# LIN_EXPO.net
KiCad netlist of a schematic drawn in Altium Designer
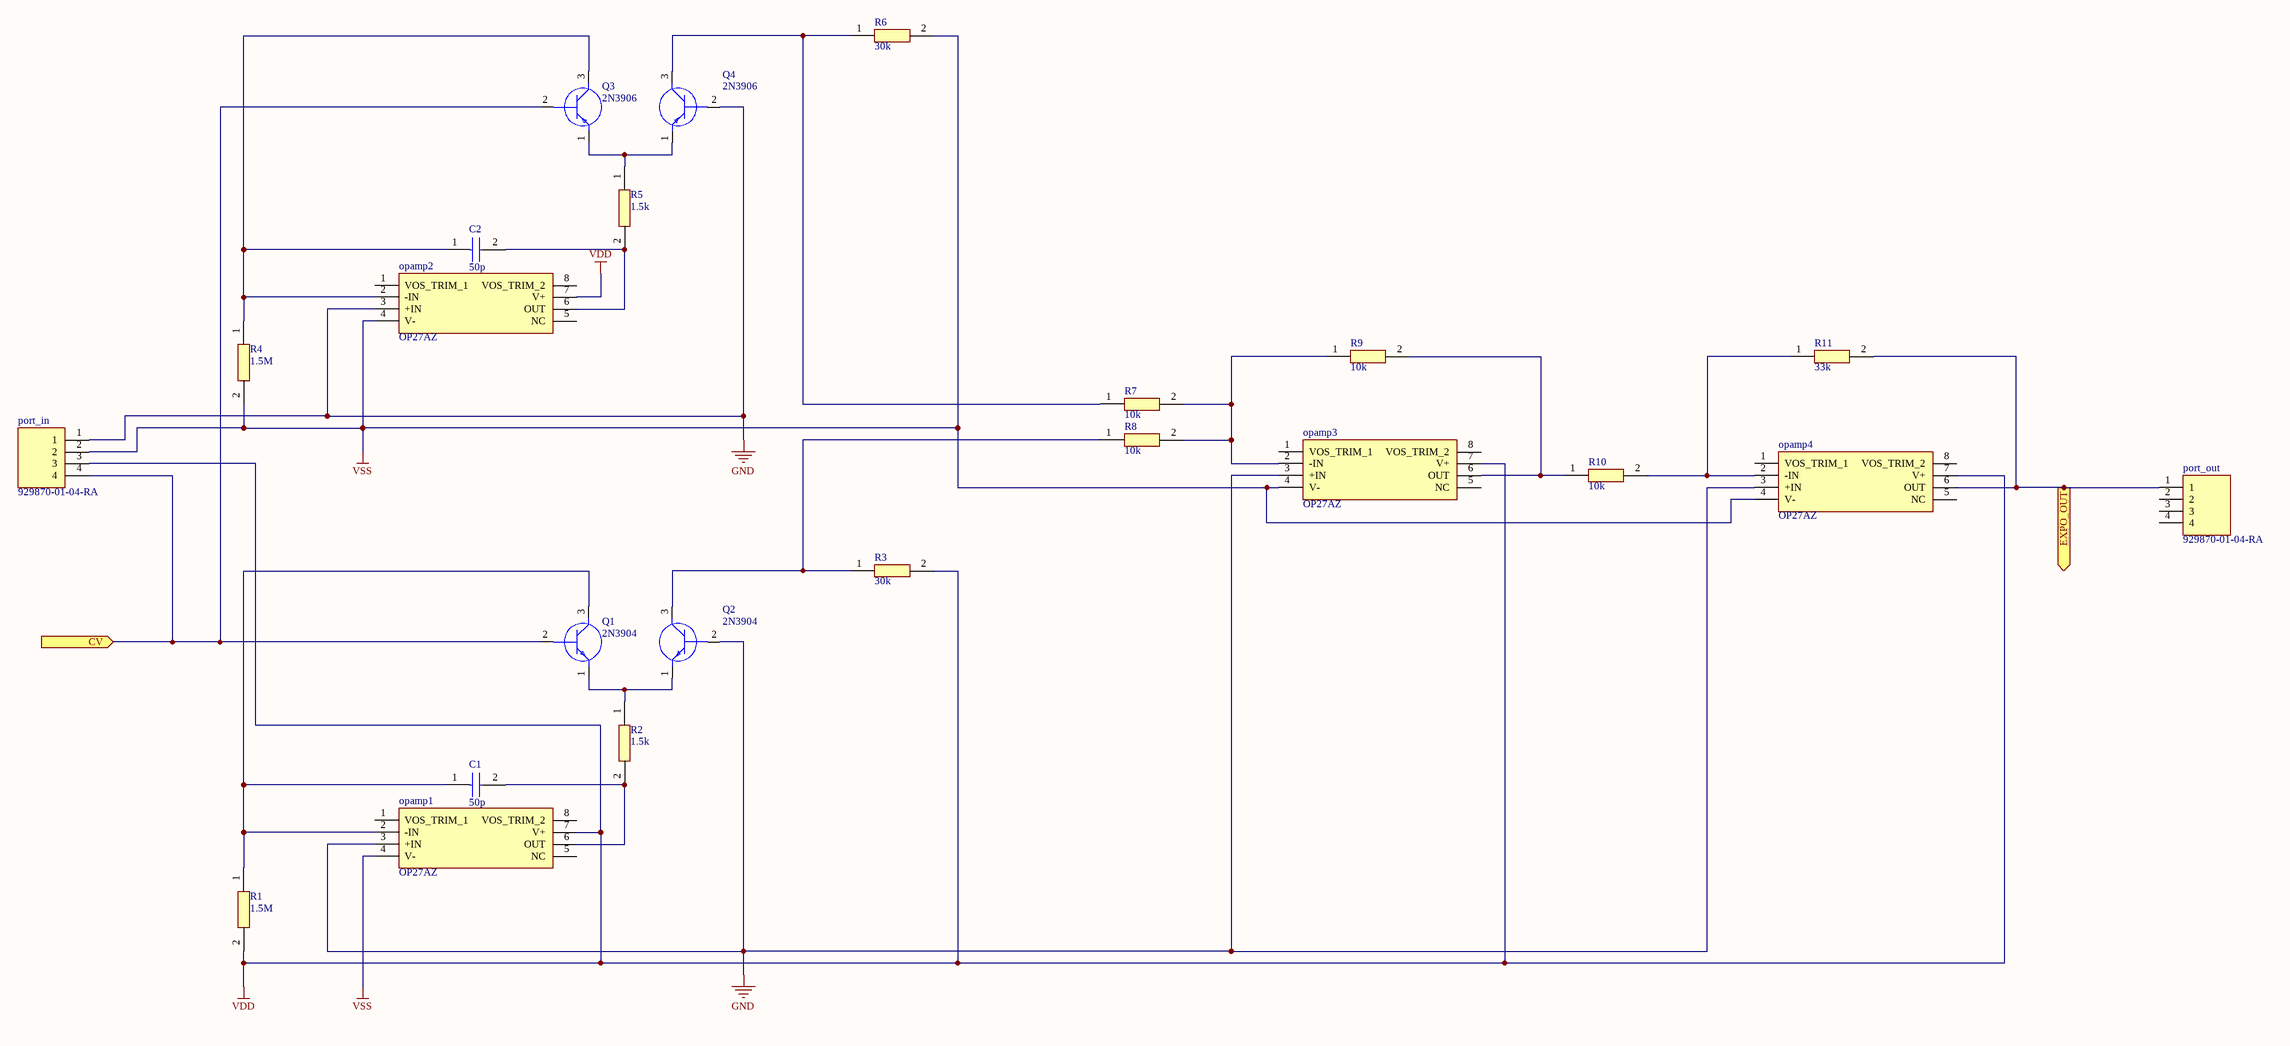
[diagram p0: LIN_EXPO.SchDoc]

(export (version "E")
  (design (tool "Eeschema 10.0.6"))
  (components
    (comp (ref "C1")
      (value "50p")
      (footprint "SamacSys:CAPPA2400W30L800D400")
      (description "Capacitor")
      (fields (field (name "MANUFACTURER_PART_NUMBER") "0113207"))
      (libsource (lib "SamacSys") (part "0113207"))
    )
    (comp (ref "C2")
      (value "50p")
      (footprint "SamacSys:CAPPA2400W30L800D400")
      (description "Capacitor")
      (fields (field (name "MANUFACTURER_PART_NUMBER") "0113207"))
      (libsource (lib "SamacSys") (part "0113207"))
    )
    (comp (ref "opamp1")
      (value "OP27AZ")
      (footprint "SamacSys:DIP775W58P254L1029H508Q8N")
      (description "Integrated Circuit")
      (fields (field (name "MOUSER PART NUMBER") "700-OP27AZNR"))
      (libsource (lib "SamacSys") (part "OP27AZ"))
    )
    (comp (ref "opamp2")
      (value "OP27AZ")
      (footprint "SamacSys:DIP775W58P254L1029H508Q8N")
      (description "Integrated Circuit")
      (fields (field (name "MOUSER PART NUMBER") "700-OP27AZNR"))
      (libsource (lib "SamacSys") (part "OP27AZ"))
    )
    (comp (ref "opamp3")
      (value "OP27AZ")
      (footprint "SamacSys:DIP775W58P254L1029H508Q8N")
      (description "Integrated Circuit")
      (fields (field (name "MOUSER PART NUMBER") "700-OP27AZNR"))
      (libsource (lib "SamacSys") (part "OP27AZ"))
    )
    (comp (ref "opamp4")
      (value "OP27AZ")
      (footprint "SamacSys:DIP775W58P254L1029H508Q8N")
      (description "Integrated Circuit")
      (fields (field (name "MOUSER PART NUMBER") "700-OP27AZNR"))
      (libsource (lib "SamacSys") (part "OP27AZ"))
    )
    (comp (ref "port_in")
      (value "929870-01-04-RA")
      (footprint "SamacSys:RHDR4W76P0X254_1X4_1016X254X826P")
      (description "Connector")
      (fields (field (name "MOUSER PART NUMBER") "517-929870-01-04-RA"))
      (libsource (lib "") (part "929870-01-04-RA_1"))
    )
    (comp (ref "port_out")
      (value "929870-01-04-RA")
      (footprint "SamacSys:RHDR4W76P0X254_1X4_1016X254X826P")
      (description "Connector")
      (fields (field (name "MOUSER PART NUMBER") "517-929870-01-04-RA"))
      (libsource (lib "SamacSys") (part "929870-01-04-RA"))
    )
    (comp (ref "Q1")
      (value "2N3904")
      (footprint "SamacSys:CS_TO-92")
      (description "Transistor BJT NPN")
      (fields (field (name "MOUSER PART NUMBER") "610-2N3904"))
      (libsource (lib "*") (part "2N3904"))
    )
    (comp (ref "Q2")
      (value "2N3904")
      (footprint "SamacSys:CS_TO-92")
      (description "Transistor BJT NPN")
      (fields (field (name "MOUSER PART NUMBER") "610-2N3904"))
      (libsource (lib "SamacSys") (part "2N3904"))
    )
    (comp (ref "Q3")
      (value "2N3906")
      (footprint "SamacSys:2N5457")
      (description "Transistor BJT PNP")
      (fields (field (name "MOUSER PART NUMBER") "610-2N3906"))
      (libsource (lib "*") (part "2N3906"))
    )
    (comp (ref "Q4")
      (value "2N3906")
      (footprint "SamacSys:2N5457")
      (description "Transistor BJT PNP")
      (fields (field (name "MOUSER PART NUMBER") "610-2N3906"))
      (libsource (lib "SamacSys") (part "2N3906"))
    )
    (comp (ref "R1")
      (value "1.5M")
      (footprint "SamacSys:RESAD1650W60L650D250")
      (description "Resistor")
      (fields
        (field (name "MANUFACTURER_PART_NUMBER") "MRS25000C1003FC100")
        (field (name "MOUSER PART NUMBER") "594-MRS25000C1003FC1")
      )
      (libsource (lib "") (part "MRS25000C1003FC100_1"))
    )
    (comp (ref "R2")
      (value "1.5k")
      (footprint "SamacSys:RESAD1650W60L650D250")
      (description "Resistor")
      (fields
        (field (name "MANUFACTURER_PART_NUMBER") "MRS25000C1003FC100")
        (field (name "MOUSER PART NUMBER") "594-MRS25000C1003FC1")
      )
      (libsource (lib "") (part "MRS25000C1003FC100_1"))
    )
    (comp (ref "R3")
      (value "30k")
      (footprint "SamacSys:RESAD1650W60L650D250")
      (description "Resistor")
      (fields
        (field (name "MANUFACTURER_PART_NUMBER") "MRS25000C1003FC100")
        (field (name "MOUSER PART NUMBER") "594-MRS25000C1003FC1")
      )
      (libsource (lib "SamacSys") (part "MRS25000C1003FC100"))
    )
    (comp (ref "R4")
      (value "1.5M")
      (footprint "SamacSys:RESAD1650W60L650D250")
      (description "Resistor")
      (fields
        (field (name "MANUFACTURER_PART_NUMBER") "MRS25000C1003FC100")
        (field (name "MOUSER PART NUMBER") "594-MRS25000C1003FC1")
      )
      (libsource (lib "") (part "MRS25000C1003FC100_1"))
    )
    (comp (ref "R5")
      (value "1.5k")
      (footprint "SamacSys:RESAD1650W60L650D250")
      (description "Resistor")
      (fields
        (field (name "MANUFACTURER_PART_NUMBER") "MRS25000C1003FC100")
        (field (name "MOUSER PART NUMBER") "594-MRS25000C1003FC1")
      )
      (libsource (lib "") (part "MRS25000C1003FC100_1"))
    )
    (comp (ref "R6")
      (value "30k")
      (footprint "SamacSys:RESAD1650W60L650D250")
      (description "Resistor")
      (fields
        (field (name "MANUFACTURER_PART_NUMBER") "MRS25000C1003FC100")
        (field (name "MOUSER PART NUMBER") "594-MRS25000C1003FC1")
      )
      (libsource (lib "SamacSys") (part "MRS25000C1003FC100"))
    )
    (comp (ref "R7")
      (value "10k")
      (footprint "SamacSys:RESAD1650W60L650D250")
      (description "Resistor")
      (fields
        (field (name "MANUFACTURER_PART_NUMBER") "MRS25000C1003FC100")
        (field (name "MOUSER PART NUMBER") "594-MRS25000C1003FC1")
      )
      (libsource (lib "SamacSys") (part "MRS25000C1003FC100"))
    )
    (comp (ref "R8")
      (value "10k")
      (footprint "SamacSys:RESAD1650W60L650D250")
      (description "Resistor")
      (fields
        (field (name "MANUFACTURER_PART_NUMBER") "MRS25000C1003FC100")
        (field (name "MOUSER PART NUMBER") "594-MRS25000C1003FC1")
      )
      (libsource (lib "SamacSys") (part "MRS25000C1003FC100"))
    )
    (comp (ref "R9")
      (value "10k")
      (footprint "SamacSys:RESAD1650W60L650D250")
      (description "Resistor")
      (fields
        (field (name "MANUFACTURER_PART_NUMBER") "MRS25000C1003FC100")
        (field (name "MOUSER PART NUMBER") "594-MRS25000C1003FC1")
      )
      (libsource (lib "SamacSys") (part "MRS25000C1003FC100"))
    )
    (comp (ref "R10")
      (value "10k")
      (footprint "SamacSys:RESAD1650W60L650D250")
      (description "Resistor")
      (fields
        (field (name "MANUFACTURER_PART_NUMBER") "MRS25000C1003FC100")
        (field (name "MOUSER PART NUMBER") "594-MRS25000C1003FC1")
      )
      (libsource (lib "SamacSys") (part "MRS25000C1003FC100"))
    )
    (comp (ref "R11")
      (value "33k")
      (footprint "SamacSys:RESAD1650W60L650D250")
      (description "Resistor")
      (fields
        (field (name "MANUFACTURER_PART_NUMBER") "MRS25000C1003FC100")
        (field (name "MOUSER PART NUMBER") "594-MRS25000C1003FC1")
      )
      (libsource (lib "SamacSys") (part "MRS25000C1003FC100"))
    )
  )
  (nets
    (net (code "1") (name "/CV") (class "Default")
      (node (ref "Q1") (pin "2") (pinfunction "B_2") (pintype "passive"))
      (node (ref "Q3") (pin "2") (pinfunction "B_2") (pintype "passive"))
      (node (ref "port_in") (pin "4") (pinfunction "4_4") (pintype "passive"))
    )
    (net (code "2") (name "/EXPO_OUT") (class "Default")
      (node (ref "R11") (pin "2") (pinfunction "2_2") (pintype "passive"))
      (node (ref "opamp4") (pin "6") (pinfunction "OUT_6") (pintype "passive"))
      (node (ref "port_out") (pin "1") (pinfunction "1_1") (pintype "passive"))
    )
    (net (code "3") (name "GND") (class "Default")
      (node (ref "Q2") (pin "2") (pinfunction "B_2") (pintype "passive"))
      (node (ref "Q4") (pin "2") (pinfunction "B_2") (pintype "passive"))
      (node (ref "opamp1") (pin "3") (pinfunction "+IN_3") (pintype "passive"))
      (node (ref "opamp2") (pin "3") (pinfunction "+IN_3") (pintype "passive"))
      (node (ref "opamp3") (pin "3") (pinfunction "+IN_3") (pintype "passive"))
      (node (ref "opamp4") (pin "3") (pinfunction "+IN_3") (pintype "passive"))
      (node (ref "port_in") (pin "1") (pinfunction "1_1") (pintype "passive"))
    )
    (net (code "4") (name "Net-(C1-+)") (class "Default")
      (node (ref "C1") (pin "1") (pinfunction "+_1") (pintype "passive"))
      (node (ref "Q1") (pin "3") (pinfunction "C_3") (pintype "passive"))
      (node (ref "R1") (pin "1") (pinfunction "1_1") (pintype "passive"))
      (node (ref "opamp1") (pin "2") (pinfunction "-IN_2") (pintype "passive"))
    )
    (net (code "5") (name "Net-(C1--)") (class "Default")
      (node (ref "C1") (pin "2") (pinfunction "-_2") (pintype "passive"))
      (node (ref "R2") (pin "2") (pinfunction "2_2") (pintype "passive"))
      (node (ref "opamp1") (pin "6") (pinfunction "OUT_6") (pintype "passive"))
    )
    (net (code "6") (name "Net-(C2-+)") (class "Default")
      (node (ref "C2") (pin "1") (pinfunction "+_1") (pintype "passive"))
      (node (ref "Q3") (pin "3") (pinfunction "C_3") (pintype "passive"))
      (node (ref "R4") (pin "1") (pinfunction "1_1") (pintype "passive"))
      (node (ref "opamp2") (pin "2") (pinfunction "-IN_2") (pintype "passive"))
    )
    (net (code "7") (name "Net-(C2--)") (class "Default")
      (node (ref "C2") (pin "2") (pinfunction "-_2") (pintype "passive"))
      (node (ref "R5") (pin "2") (pinfunction "2_2") (pintype "passive"))
      (node (ref "opamp2") (pin "6") (pinfunction "OUT_6") (pintype "passive"))
    )
    (net (code "8") (name "Net-(Q1-E)") (class "Default")
      (node (ref "Q1") (pin "1") (pinfunction "E_1") (pintype "passive"))
      (node (ref "Q2") (pin "1") (pinfunction "E_1") (pintype "passive"))
      (node (ref "R2") (pin "1") (pinfunction "1_1") (pintype "passive"))
    )
    (net (code "9") (name "Net-(Q2-C)") (class "Default")
      (node (ref "Q2") (pin "3") (pinfunction "C_3") (pintype "passive"))
      (node (ref "R3") (pin "1") (pinfunction "1_1") (pintype "passive"))
      (node (ref "R8") (pin "1") (pinfunction "1_1") (pintype "passive"))
    )
    (net (code "10") (name "Net-(Q3-E)") (class "Default")
      (node (ref "Q3") (pin "1") (pinfunction "E_1") (pintype "passive"))
      (node (ref "Q4") (pin "1") (pinfunction "E_1") (pintype "passive"))
      (node (ref "R5") (pin "1") (pinfunction "1_1") (pintype "passive"))
    )
    (net (code "11") (name "Net-(Q4-C)") (class "Default")
      (node (ref "Q4") (pin "3") (pinfunction "C_3") (pintype "passive"))
      (node (ref "R6") (pin "1") (pinfunction "1_1") (pintype "passive"))
      (node (ref "R7") (pin "1") (pinfunction "1_1") (pintype "passive"))
    )
    (net (code "12") (name "Net-(opamp3--IN)") (class "Default")
      (node (ref "R7") (pin "2") (pinfunction "2_2") (pintype "passive"))
      (node (ref "R8") (pin "2") (pinfunction "2_2") (pintype "passive"))
      (node (ref "R9") (pin "1") (pinfunction "1_1") (pintype "passive"))
      (node (ref "opamp3") (pin "2") (pinfunction "-IN_2") (pintype "passive"))
    )
    (net (code "13") (name "Net-(opamp3-OUT)") (class "Default")
      (node (ref "R10") (pin "1") (pinfunction "1_1") (pintype "passive"))
      (node (ref "R9") (pin "2") (pinfunction "2_2") (pintype "passive"))
      (node (ref "opamp3") (pin "6") (pinfunction "OUT_6") (pintype "passive"))
    )
    (net (code "14") (name "Net-(opamp4--IN)") (class "Default")
      (node (ref "R10") (pin "2") (pinfunction "2_2") (pintype "passive"))
      (node (ref "R11") (pin "1") (pinfunction "1_1") (pintype "passive"))
      (node (ref "opamp4") (pin "2") (pinfunction "-IN_2") (pintype "passive"))
    )
    (net (code "15") (name "VDD") (class "Default")
      (node (ref "R1") (pin "2") (pinfunction "2_2") (pintype "passive"))
      (node (ref "R3") (pin "2") (pinfunction "2_2") (pintype "passive"))
      (node (ref "opamp1") (pin "7") (pinfunction "V+_7") (pintype "passive"))
      (node (ref "opamp2") (pin "7") (pinfunction "V+_7") (pintype "passive"))
      (node (ref "opamp3") (pin "7") (pinfunction "V+_7") (pintype "passive"))
      (node (ref "opamp4") (pin "7") (pinfunction "V+_7") (pintype "passive"))
      (node (ref "port_in") (pin "3") (pinfunction "3_3") (pintype "passive"))
    )
    (net (code "16") (name "VSS") (class "Default")
      (node (ref "R4") (pin "2") (pinfunction "2_2") (pintype "passive"))
      (node (ref "R6") (pin "2") (pinfunction "2_2") (pintype "passive"))
      (node (ref "opamp1") (pin "4") (pinfunction "V-_4") (pintype "passive"))
      (node (ref "opamp2") (pin "4") (pinfunction "V-_4") (pintype "passive"))
      (node (ref "opamp3") (pin "4") (pinfunction "V-_4") (pintype "passive"))
      (node (ref "opamp4") (pin "4") (pinfunction "V-_4") (pintype "passive"))
      (node (ref "port_in") (pin "2") (pinfunction "2_2") (pintype "passive"))
    )
    (net (code "17") (name "unconnected-(opamp1-NC-Pad5)") (class "Default")
      (node (ref "opamp1") (pin "5") (pinfunction "NC_5") (pintype "passive"))
    )
    (net (code "18") (name "unconnected-(opamp1-VOS_TRIM_1-Pad1)") (class "Default")
      (node (ref "opamp1") (pin "1") (pinfunction "VOS_TRIM_1_1") (pintype "passive"))
    )
    (net (code "19") (name "unconnected-(opamp1-VOS_TRIM_2-Pad8)") (class "Default")
      (node (ref "opamp1") (pin "8") (pinfunction "VOS_TRIM_2_8") (pintype "passive"))
    )
    (net (code "20") (name "unconnected-(opamp2-NC-Pad5)") (class "Default")
      (node (ref "opamp2") (pin "5") (pinfunction "NC_5") (pintype "passive"))
    )
    (net (code "21") (name "unconnected-(opamp2-VOS_TRIM_1-Pad1)") (class "Default")
      (node (ref "opamp2") (pin "1") (pinfunction "VOS_TRIM_1_1") (pintype "passive"))
    )
    (net (code "22") (name "unconnected-(opamp2-VOS_TRIM_2-Pad8)") (class "Default")
      (node (ref "opamp2") (pin "8") (pinfunction "VOS_TRIM_2_8") (pintype "passive"))
    )
    (net (code "23") (name "unconnected-(opamp3-NC-Pad5)") (class "Default")
      (node (ref "opamp3") (pin "5") (pinfunction "NC_5") (pintype "passive"))
    )
    (net (code "24") (name "unconnected-(opamp3-VOS_TRIM_1-Pad1)") (class "Default")
      (node (ref "opamp3") (pin "1") (pinfunction "VOS_TRIM_1_1") (pintype "passive"))
    )
    (net (code "25") (name "unconnected-(opamp3-VOS_TRIM_2-Pad8)") (class "Default")
      (node (ref "opamp3") (pin "8") (pinfunction "VOS_TRIM_2_8") (pintype "passive"))
    )
    (net (code "26") (name "unconnected-(opamp4-NC-Pad5)") (class "Default")
      (node (ref "opamp4") (pin "5") (pinfunction "NC_5") (pintype "passive"))
    )
    (net (code "27") (name "unconnected-(opamp4-VOS_TRIM_1-Pad1)") (class "Default")
      (node (ref "opamp4") (pin "1") (pinfunction "VOS_TRIM_1_1") (pintype "passive"))
    )
    (net (code "28") (name "unconnected-(opamp4-VOS_TRIM_2-Pad8)") (class "Default")
      (node (ref "opamp4") (pin "8") (pinfunction "VOS_TRIM_2_8") (pintype "passive"))
    )
    (net (code "29") (name "unconnected-(port_out-Pad2)") (class "Default")
      (node (ref "port_out") (pin "2") (pinfunction "2_2") (pintype "passive"))
    )
    (net (code "30") (name "unconnected-(port_out-Pad3)") (class "Default")
      (node (ref "port_out") (pin "3") (pinfunction "3_3") (pintype "passive"))
    )
    (net (code "31") (name "unconnected-(port_out-Pad4)") (class "Default")
      (node (ref "port_out") (pin "4") (pinfunction "4_4") (pintype "passive"))
    )
  )
)
